# M891.net
KiCad netlist of a schematic drawn in EAGLE
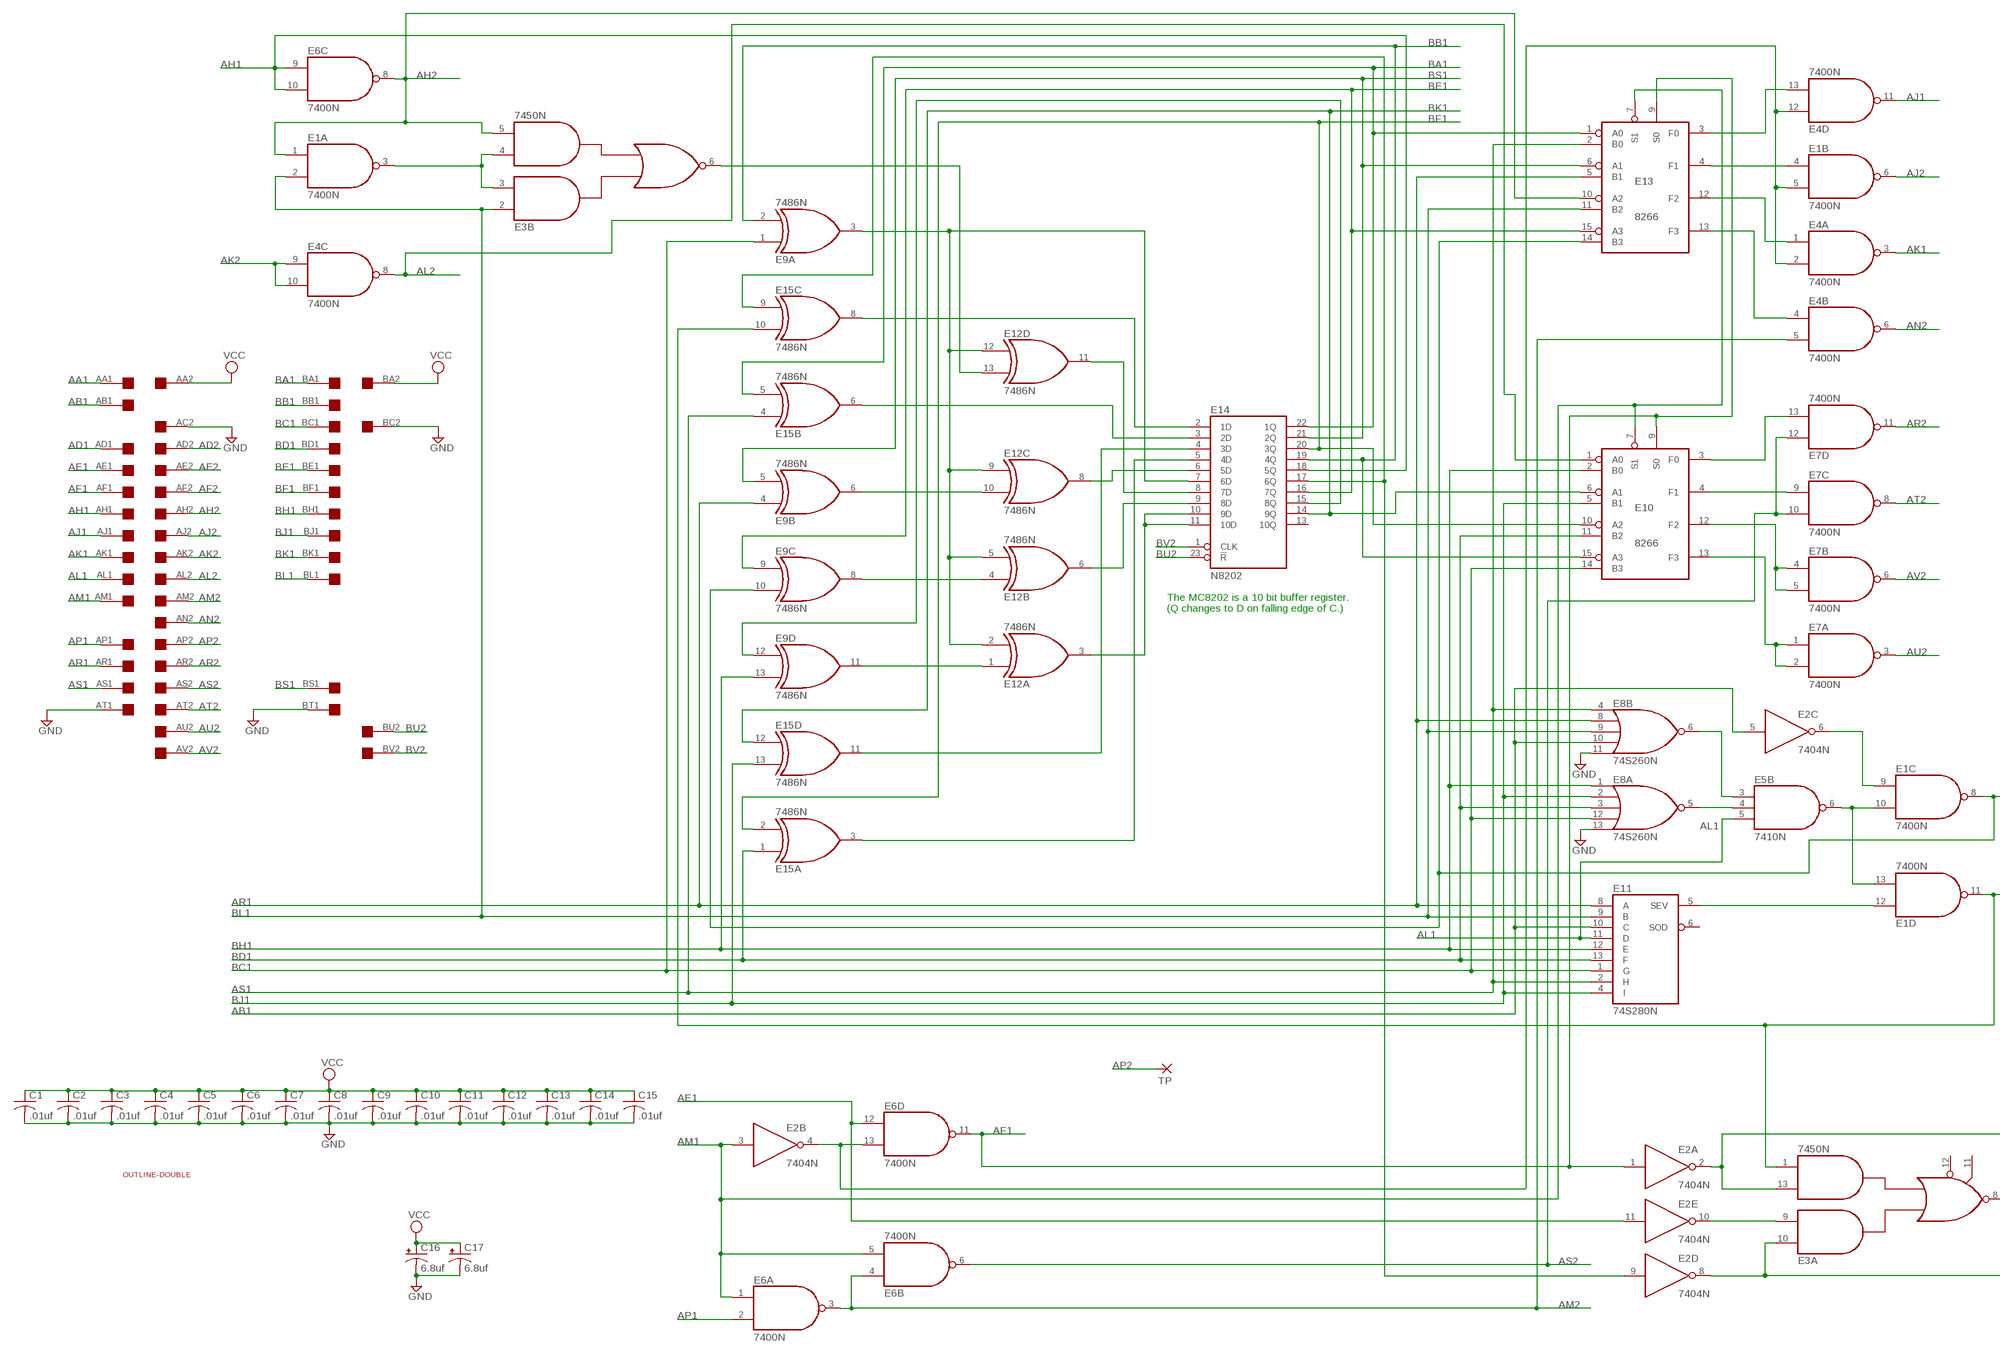
[diagram p0: schematic, sheet 1, part 1 of 2]
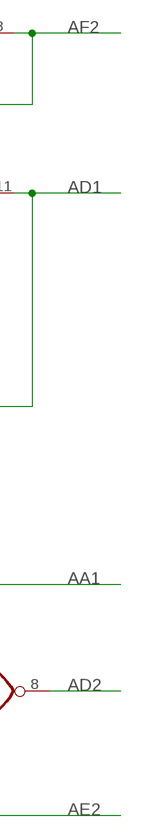
[diagram p1: schematic, sheet 1, part 2 of 2]

(export (version "E")
  (design (tool "Eeschema 10.0.6"))
  (components
    (comp (ref "C1")
      (value ".01uf")
      (footprint "eagle-import:C050-025X075")
      (libsource (lib "eagle-import") (part "C-US050-025X075"))
    )
    (comp (ref "C2")
      (value ".01uf")
      (footprint "eagle-import:C050-025X075")
      (libsource (lib "eagle-import") (part "C-US050-025X075"))
    )
    (comp (ref "C3")
      (value ".01uf")
      (footprint "eagle-import:C050-025X075")
      (libsource (lib "eagle-import") (part "C-US050-025X075"))
    )
    (comp (ref "C4")
      (value ".01uf")
      (footprint "eagle-import:C050-025X075")
      (libsource (lib "eagle-import") (part "C-US050-025X075"))
    )
    (comp (ref "C5")
      (value ".01uf")
      (footprint "eagle-import:C050-025X075")
      (libsource (lib "eagle-import") (part "C-US050-025X075"))
    )
    (comp (ref "C6")
      (value ".01uf")
      (footprint "eagle-import:C050-025X075")
      (libsource (lib "eagle-import") (part "C-US050-025X075"))
    )
    (comp (ref "C7")
      (value ".01uf")
      (footprint "eagle-import:C050-025X075")
      (libsource (lib "eagle-import") (part "C-US050-025X075"))
    )
    (comp (ref "C8")
      (value ".01uf")
      (footprint "eagle-import:C050-025X075")
      (libsource (lib "eagle-import") (part "C-US050-025X075"))
    )
    (comp (ref "C9")
      (value ".01uf")
      (footprint "eagle-import:C050-025X075")
      (libsource (lib "eagle-import") (part "C-US050-025X075"))
    )
    (comp (ref "C10")
      (value ".01uf")
      (footprint "eagle-import:C050-025X075")
      (libsource (lib "eagle-import") (part "C-US050-025X075"))
    )
    (comp (ref "C11")
      (value ".01uf")
      (footprint "eagle-import:C050-025X075")
      (libsource (lib "eagle-import") (part "C-US050-025X075"))
    )
    (comp (ref "C12")
      (value ".01uf")
      (footprint "eagle-import:C050-025X075")
      (libsource (lib "eagle-import") (part "C-US050-025X075"))
    )
    (comp (ref "C13")
      (value ".01uf")
      (footprint "eagle-import:C050-025X075")
      (libsource (lib "eagle-import") (part "C-US050-025X075"))
    )
    (comp (ref "C14")
      (value ".01uf")
      (footprint "eagle-import:C050-025X075")
      (libsource (lib "eagle-import") (part "C-US050-025X075"))
    )
    (comp (ref "C15")
      (value ".01uf")
      (footprint "eagle-import:C050-025X075")
      (libsource (lib "eagle-import") (part "C-US050-025X075"))
    )
    (comp (ref "C16")
      (value "6.8uf")
      (footprint "eagle-import:E22-6")
      (libsource (lib "eagle-import") (part "CPOL-USE22-6AXIAL"))
    )
    (comp (ref "C17")
      (value "6.8uf")
      (footprint "eagle-import:E22-6")
      (libsource (lib "eagle-import") (part "CPOL-USE22-6AXIAL"))
    )
    (comp (ref "E1")
      (value "7400N")
      (footprint "eagle-import:DIL14")
      (libsource (lib "eagle-import") (part "7400N"))
    )
    (comp (ref "E2")
      (value "7404N")
      (footprint "eagle-import:DIL14")
      (libsource (lib "eagle-import") (part "7404N"))
    )
    (comp (ref "E3")
      (value "7450N")
      (footprint "eagle-import:DIL14")
      (libsource (lib "eagle-import") (part "7450N"))
    )
    (comp (ref "E4")
      (value "7400N")
      (footprint "eagle-import:DIL14")
      (libsource (lib "eagle-import") (part "7400N"))
    )
    (comp (ref "E5")
      (value "7410N")
      (footprint "eagle-import:DIL14")
      (libsource (lib "eagle-import") (part "7410N"))
    )
    (comp (ref "E6")
      (value "7400N")
      (footprint "eagle-import:DIL14")
      (libsource (lib "eagle-import") (part "7400N"))
    )
    (comp (ref "E7")
      (value "7400N")
      (footprint "eagle-import:DIL14")
      (libsource (lib "eagle-import") (part "7400N"))
    )
    (comp (ref "E8")
      (value "74S260N")
      (footprint "eagle-import:DIL14")
      (libsource (lib "eagle-import") (part "74260NS"))
    )
    (comp (ref "E9")
      (value "7486N")
      (footprint "eagle-import:DIL14")
      (libsource (lib "eagle-import") (part "7486N"))
    )
    (comp (ref "E10")
      (value "8266")
      (footprint "eagle-import:DIL16")
      (libsource (lib "eagle-import") (part "8266"))
    )
    (comp (ref "E11")
      (value "74S280N")
      (footprint "eagle-import:DIL14")
      (libsource (lib "eagle-import") (part "74280NS"))
    )
    (comp (ref "E12")
      (value "7486N")
      (footprint "eagle-import:DIL14")
      (libsource (lib "eagle-import") (part "7486N"))
    )
    (comp (ref "E13")
      (value "8266")
      (footprint "eagle-import:DIL16")
      (libsource (lib "eagle-import") (part "8266"))
    )
    (comp (ref "E14")
      (value "N8202")
      (footprint "eagle-import:DIL24")
      (libsource (lib "eagle-import") (part "N8202"))
    )
    (comp (ref "E15")
      (value "7486N")
      (footprint "eagle-import:DIL14")
      (libsource (lib "eagle-import") (part "7486N"))
    )
    (comp (ref "EDGE")
      (value "DOUBLE")
      (footprint "eagle-import:EDGE-CON4")
      (libsource (lib "eagle-import") (part "DOUBLE"))
    )
    (comp (ref "TP")
      (value "2,15/1,0")
      (footprint "eagle-import:2,15_1,0")
      (libsource (lib "eagle-import") (part "2,15/1,0"))
    )
    (comp (ref "U$2")
      (value "OUTLINE-DOUBLE")
      (footprint "eagle-import:DOUBLE")
      (libsource (lib "eagle-import") (part "OUTLINE-DOUBLE"))
    )
  )
  (nets
    (net (code "1") (name "/AA1") (class "Default")
      (node (ref "E2") (pin "2") (pinfunction "O_2") (pintype "output"))
      (node (ref "E3") (pin "13") (pinfunction "I3_13") (pintype "input"))
      (node (ref "EDGE") (pin "AA1") (pinfunction "1_AA1") (pintype "bidirectional"))
    )
    (net (code "2") (name "/AB1") (class "Default")
      (node (ref "E11") (pin "10") (pinfunction "C_10") (pintype "input"))
      (node (ref "E2") (pin "5") (pinfunction "I_5") (pintype "input"))
      (node (ref "E8") (pin "10") (pinfunction "I3_10") (pintype "input"))
      (node (ref "EDGE") (pin "AB1") (pinfunction "1_AB1") (pintype "bidirectional"))
    )
    (net (code "3") (name "/AD1") (class "Default")
      (node (ref "E1") (pin "11") (pinfunction "O_11") (pintype "output"))
      (node (ref "E15") (pin "10") (pinfunction "I1_10") (pintype "input"))
      (node (ref "E3") (pin "1") (pinfunction "I4_1") (pintype "input"))
      (node (ref "EDGE") (pin "AD1") (pinfunction "1_AD1") (pintype "bidirectional"))
    )
    (net (code "4") (name "/AD2") (class "Default")
      (node (ref "E3") (pin "8") (pinfunction "O_8") (pintype "output"))
      (node (ref "EDGE") (pin "AD2") (pinfunction "1_AD2") (pintype "bidirectional"))
    )
    (net (code "5") (name "/AE1") (class "Default")
      (node (ref "E2") (pin "11") (pinfunction "I_11") (pintype "input"))
      (node (ref "E6") (pin "12") (pinfunction "I0_12") (pintype "input"))
      (node (ref "EDGE") (pin "AE1") (pinfunction "1_AE1") (pintype "bidirectional"))
    )
    (net (code "6") (name "/AE2") (class "Default")
      (node (ref "E2") (pin "8") (pinfunction "O_8") (pintype "output"))
      (node (ref "E3") (pin "10") (pinfunction "I1_10") (pintype "input"))
      (node (ref "EDGE") (pin "AE2") (pinfunction "1_AE2") (pintype "bidirectional"))
    )
    (net (code "7") (name "/AF1") (class "Default")
      (node (ref "E10") (pin "9") (pinfunction "S0_9") (pintype "input"))
      (node (ref "E13") (pin "9") (pinfunction "S0_9") (pintype "input"))
      (node (ref "E2") (pin "1") (pinfunction "I_1") (pintype "input"))
      (node (ref "E6") (pin "11") (pinfunction "O_11") (pintype "output"))
      (node (ref "EDGE") (pin "AF1") (pinfunction "1_AF1") (pintype "bidirectional"))
    )
    (net (code "8") (name "/AF2") (class "Default")
      (node (ref "E1") (pin "8") (pinfunction "O_8") (pintype "output"))
      (node (ref "E13") (pin "14") (pinfunction "B3_14") (pintype "input"))
      (node (ref "E9") (pin "10") (pinfunction "I1_10") (pintype "input"))
      (node (ref "EDGE") (pin "AF2") (pinfunction "1_AF2") (pintype "bidirectional"))
    )
    (net (code "9") (name "/AH1") (class "Default")
      (node (ref "E14") (pin "18") (pinfunction "5Q_18") (pintype "tri_state"))
      (node (ref "E6") (pin "10") (pinfunction "I1_10") (pintype "input"))
      (node (ref "E6") (pin "9") (pinfunction "I0_9") (pintype "input"))
      (node (ref "EDGE") (pin "AH1") (pinfunction "1_AH1") (pintype "bidirectional"))
    )
    (net (code "10") (name "/AH2") (class "Default")
      (node (ref "E1") (pin "1") (pinfunction "I0_1") (pintype "input"))
      (node (ref "E13") (pin "10") (pinfunction "A2_10") (pintype "input"))
      (node (ref "E3") (pin "5") (pinfunction "I4_5") (pintype "input"))
      (node (ref "E6") (pin "8") (pinfunction "O_8") (pintype "output"))
      (node (ref "EDGE") (pin "AH2") (pinfunction "1_AH2") (pintype "bidirectional"))
    )
    (net (code "11") (name "/AJ1") (class "Default")
      (node (ref "E4") (pin "11") (pinfunction "O_11") (pintype "output"))
      (node (ref "EDGE") (pin "AJ1") (pinfunction "1_AJ1") (pintype "bidirectional"))
    )
    (net (code "12") (name "/AJ2") (class "Default")
      (node (ref "E1") (pin "6") (pinfunction "O_6") (pintype "output"))
      (node (ref "EDGE") (pin "AJ2") (pinfunction "1_AJ2") (pintype "bidirectional"))
    )
    (net (code "13") (name "/AK1") (class "Default")
      (node (ref "E4") (pin "3") (pinfunction "O_3") (pintype "output"))
      (node (ref "EDGE") (pin "AK1") (pinfunction "1_AK1") (pintype "bidirectional"))
    )
    (net (code "14") (name "/AK2") (class "Default")
      (node (ref "E4") (pin "10") (pinfunction "I1_10") (pintype "input"))
      (node (ref "E4") (pin "9") (pinfunction "I0_9") (pintype "input"))
      (node (ref "EDGE") (pin "AK2") (pinfunction "1_AK2") (pintype "bidirectional"))
    )
    (net (code "15") (name "/AL1") (class "Default")
      (node (ref "E11") (pin "11") (pinfunction "D_11") (pintype "input"))
      (node (ref "E5") (pin "5") (pinfunction "I2_5") (pintype "input"))
      (node (ref "EDGE") (pin "AL1") (pinfunction "1_AL1") (pintype "bidirectional"))
    )
    (net (code "16") (name "/AL2") (class "Default")
      (node (ref "E10") (pin "1") (pinfunction "A0_1") (pintype "input"))
      (node (ref "E4") (pin "8") (pinfunction "O_8") (pintype "output"))
      (node (ref "EDGE") (pin "AL2") (pinfunction "1_AL2") (pintype "bidirectional"))
    )
    (net (code "17") (name "/AM1") (class "Default")
      (node (ref "E10") (pin "7") (pinfunction "S1_7") (pintype "input"))
      (node (ref "E13") (pin "7") (pinfunction "S1_7") (pintype "input"))
      (node (ref "E2") (pin "3") (pinfunction "I_3") (pintype "input"))
      (node (ref "E6") (pin "1") (pinfunction "I0_1") (pintype "input"))
      (node (ref "E6") (pin "5") (pinfunction "I1_5") (pintype "input"))
      (node (ref "EDGE") (pin "AM1") (pinfunction "1_AM1") (pintype "bidirectional"))
    )
    (net (code "18") (name "/AM2") (class "Default")
      (node (ref "E4") (pin "5") (pinfunction "I1_5") (pintype "input"))
      (node (ref "E6") (pin "3") (pinfunction "O_3") (pintype "output"))
      (node (ref "E6") (pin "4") (pinfunction "I0_4") (pintype "input"))
      (node (ref "EDGE") (pin "AM2") (pinfunction "1_AM2") (pintype "bidirectional"))
    )
    (net (code "19") (name "/AN2") (class "Default")
      (node (ref "E4") (pin "6") (pinfunction "O_6") (pintype "output"))
      (node (ref "EDGE") (pin "AN2") (pinfunction "1_AN2") (pintype "bidirectional"))
    )
    (net (code "20") (name "/AP1") (class "Default")
      (node (ref "E6") (pin "2") (pinfunction "I1_2") (pintype "input"))
      (node (ref "EDGE") (pin "AP1") (pinfunction "1_AP1") (pintype "bidirectional"))
    )
    (net (code "21") (name "/AP2") (class "Default")
      (node (ref "EDGE") (pin "AP2") (pinfunction "1_AP2") (pintype "bidirectional"))
      (node (ref "TP") (pin "1") (pinfunction "P_1") (pintype "passive"))
    )
    (net (code "22") (name "/AR1") (class "Default")
      (node (ref "E11") (pin "8") (pinfunction "A_8") (pintype "input"))
      (node (ref "E13") (pin "5") (pinfunction "B1_5") (pintype "input"))
      (node (ref "E8") (pin "8") (pinfunction "I1_8") (pintype "input"))
      (node (ref "E9") (pin "4") (pinfunction "I0_4") (pintype "input"))
      (node (ref "EDGE") (pin "AR1") (pinfunction "1_AR1") (pintype "bidirectional"))
    )
    (net (code "23") (name "/AR2") (class "Default")
      (node (ref "E7") (pin "11") (pinfunction "O_11") (pintype "output"))
      (node (ref "EDGE") (pin "AR2") (pinfunction "1_AR2") (pintype "bidirectional"))
    )
    (net (code "24") (name "/AS1") (class "Default")
      (node (ref "E11") (pin "2") (pinfunction "H_2") (pintype "input"))
      (node (ref "E13") (pin "2") (pinfunction "B0_2") (pintype "input"))
      (node (ref "E15") (pin "4") (pinfunction "I0_4") (pintype "input"))
      (node (ref "E8") (pin "4") (pinfunction "I0_4") (pintype "input"))
      (node (ref "EDGE") (pin "AS1") (pinfunction "1_AS1") (pintype "bidirectional"))
    )
    (net (code "25") (name "/AS2") (class "Default")
      (node (ref "E6") (pin "6") (pinfunction "O_6") (pintype "output"))
      (node (ref "E7") (pin "10") (pinfunction "I1_10") (pintype "input"))
      (node (ref "E7") (pin "12") (pinfunction "I0_12") (pintype "input"))
      (node (ref "EDGE") (pin "AS2") (pinfunction "1_AS2") (pintype "bidirectional"))
    )
    (net (code "26") (name "/AT2") (class "Default")
      (node (ref "E7") (pin "8") (pinfunction "O_8") (pintype "output"))
      (node (ref "EDGE") (pin "AT2") (pinfunction "1_AT2") (pintype "bidirectional"))
    )
    (net (code "27") (name "/AU2") (class "Default")
      (node (ref "E7") (pin "3") (pinfunction "O_3") (pintype "output"))
      (node (ref "EDGE") (pin "AU2") (pinfunction "1_AU2") (pintype "bidirectional"))
    )
    (net (code "28") (name "/AV2") (class "Default")
      (node (ref "E7") (pin "6") (pinfunction "O_6") (pintype "output"))
      (node (ref "EDGE") (pin "AV2") (pinfunction "1_AV2") (pintype "bidirectional"))
    )
    (net (code "29") (name "/BA1") (class "Default")
      (node (ref "E13") (pin "1") (pinfunction "A0_1") (pintype "input"))
      (node (ref "E14") (pin "22") (pinfunction "1Q_22") (pintype "tri_state"))
      (node (ref "E15") (pin "5") (pinfunction "I1_5") (pintype "input"))
      (node (ref "EDGE") (pin "BA1") (pinfunction "1_BA1") (pintype "bidirectional"))
    )
    (net (code "30") (name "/BB1") (class "Default")
      (node (ref "E10") (pin "15") (pinfunction "A3_15") (pintype "input"))
      (node (ref "E14") (pin "19") (pinfunction "4Q_19") (pintype "tri_state"))
      (node (ref "E9") (pin "2") (pinfunction "I1_2") (pintype "input"))
      (node (ref "EDGE") (pin "BB1") (pinfunction "1_BB1") (pintype "bidirectional"))
    )
    (net (code "31") (name "/BC1") (class "Default")
      (node (ref "E10") (pin "14") (pinfunction "B3_14") (pintype "input"))
      (node (ref "E11") (pin "1") (pinfunction "G_1") (pintype "input"))
      (node (ref "E8") (pin "12") (pinfunction "I3_12") (pintype "input"))
      (node (ref "E9") (pin "1") (pinfunction "I0_1") (pintype "input"))
      (node (ref "EDGE") (pin "BC1") (pinfunction "1_BC1") (pintype "bidirectional"))
    )
    (net (code "32") (name "/BD1") (class "Default")
      (node (ref "E10") (pin "11") (pinfunction "B2_11") (pintype "input"))
      (node (ref "E11") (pin "13") (pinfunction "F_13") (pintype "input"))
      (node (ref "E15") (pin "1") (pinfunction "I0_1") (pintype "input"))
      (node (ref "E8") (pin "3") (pinfunction "I2_3") (pintype "input"))
      (node (ref "EDGE") (pin "BD1") (pinfunction "1_BD1") (pintype "bidirectional"))
    )
    (net (code "33") (name "/BE1") (class "Default")
      (node (ref "E13") (pin "15") (pinfunction "A3_15") (pintype "input"))
      (node (ref "E14") (pin "16") (pinfunction "7Q_16") (pintype "tri_state"))
      (node (ref "E9") (pin "9") (pinfunction "I0_9") (pintype "input"))
      (node (ref "EDGE") (pin "BE1") (pinfunction "1_BE1") (pintype "bidirectional"))
    )
    (net (code "34") (name "/BF1") (class "Default")
      (node (ref "E10") (pin "10") (pinfunction "A2_10") (pintype "input"))
      (node (ref "E14") (pin "20") (pinfunction "3Q_20") (pintype "tri_state"))
      (node (ref "E15") (pin "2") (pinfunction "I1_2") (pintype "input"))
      (node (ref "EDGE") (pin "BF1") (pinfunction "1_BF1") (pintype "bidirectional"))
    )
    (net (code "35") (name "/BH1") (class "Default")
      (node (ref "E10") (pin "2") (pinfunction "B0_2") (pintype "input"))
      (node (ref "E11") (pin "12") (pinfunction "E_12") (pintype "input"))
      (node (ref "E8") (pin "1") (pinfunction "I0_1") (pintype "input"))
      (node (ref "E9") (pin "13") (pinfunction "I1_13") (pintype "input"))
      (node (ref "EDGE") (pin "BH1") (pinfunction "1_BH1") (pintype "bidirectional"))
    )
    (net (code "36") (name "/BJ1") (class "Default")
      (node (ref "E10") (pin "5") (pinfunction "B1_5") (pintype "input"))
      (node (ref "E11") (pin "4") (pinfunction "I_4") (pintype "input"))
      (node (ref "E15") (pin "13") (pinfunction "I1_13") (pintype "input"))
      (node (ref "E8") (pin "2") (pinfunction "I1_2") (pintype "input"))
      (node (ref "EDGE") (pin "BJ1") (pinfunction "1_BJ1") (pintype "bidirectional"))
    )
    (net (code "37") (name "/BK1") (class "Default")
      (node (ref "E10") (pin "6") (pinfunction "A1_6") (pintype "input"))
      (node (ref "E14") (pin "14") (pinfunction "9Q_14") (pintype "tri_state"))
      (node (ref "E15") (pin "12") (pinfunction "I0_12") (pintype "input"))
      (node (ref "EDGE") (pin "BK1") (pinfunction "1_BK1") (pintype "bidirectional"))
    )
    (net (code "38") (name "/BL1") (class "Default")
      (node (ref "E1") (pin "2") (pinfunction "I1_2") (pintype "input"))
      (node (ref "E11") (pin "9") (pinfunction "B_9") (pintype "input"))
      (node (ref "E13") (pin "11") (pinfunction "B2_11") (pintype "input"))
      (node (ref "E3") (pin "2") (pinfunction "I1_2") (pintype "input"))
      (node (ref "E8") (pin "9") (pinfunction "I2_9") (pintype "input"))
      (node (ref "EDGE") (pin "BL1") (pinfunction "1_BL1") (pintype "bidirectional"))
    )
    (net (code "39") (name "/BS1") (class "Default")
      (node (ref "E13") (pin "6") (pinfunction "A1_6") (pintype "input"))
      (node (ref "E14") (pin "21") (pinfunction "2Q_21") (pintype "tri_state"))
      (node (ref "E9") (pin "5") (pinfunction "I1_5") (pintype "input"))
      (node (ref "EDGE") (pin "BS1") (pinfunction "1_BS1") (pintype "bidirectional"))
    )
    (net (code "40") (name "/BU2") (class "Default")
      (node (ref "E14") (pin "23") (pinfunction "~{R}_23") (pintype "input"))
      (node (ref "EDGE") (pin "BU2") (pinfunction "1_BU2") (pintype "bidirectional"))
    )
    (net (code "41") (name "/BV2") (class "Default")
      (node (ref "E14") (pin "1") (pinfunction "CLK_1") (pintype "input"))
      (node (ref "EDGE") (pin "BV2") (pinfunction "1_BV2") (pintype "bidirectional"))
    )
    (net (code "42") (name "GND") (class "Default")
      (node (ref "C1") (pin "2") (pinfunction "2_2") (pintype "passive"))
      (node (ref "C10") (pin "2") (pinfunction "2_2") (pintype "passive"))
      (node (ref "C11") (pin "2") (pinfunction "2_2") (pintype "passive"))
      (node (ref "C12") (pin "2") (pinfunction "2_2") (pintype "passive"))
      (node (ref "C13") (pin "2") (pinfunction "2_2") (pintype "passive"))
      (node (ref "C14") (pin "2") (pinfunction "2_2") (pintype "passive"))
      (node (ref "C15") (pin "2") (pinfunction "2_2") (pintype "passive"))
      (node (ref "C16") (pin "-") (pinfunction "-_-") (pintype "passive"))
      (node (ref "C17") (pin "-") (pinfunction "-_-") (pintype "passive"))
      (node (ref "C2") (pin "2") (pinfunction "2_2") (pintype "passive"))
      (node (ref "C3") (pin "2") (pinfunction "2_2") (pintype "passive"))
      (node (ref "C4") (pin "2") (pinfunction "2_2") (pintype "passive"))
      (node (ref "C5") (pin "2") (pinfunction "2_2") (pintype "passive"))
      (node (ref "C6") (pin "2") (pinfunction "2_2") (pintype "passive"))
      (node (ref "C7") (pin "2") (pinfunction "2_2") (pintype "passive"))
      (node (ref "C8") (pin "2") (pinfunction "2_2") (pintype "passive"))
      (node (ref "C9") (pin "2") (pinfunction "2_2") (pintype "passive"))
      (node (ref "E8") (pin "11") (pinfunction "I4_11") (pintype "input"))
      (node (ref "E8") (pin "13") (pinfunction "I4_13") (pintype "input"))
      (node (ref "EDGE") (pin "AC2") (pinfunction "1_AC2") (pintype "bidirectional"))
      (node (ref "EDGE") (pin "AT1") (pinfunction "1_AT1") (pintype "bidirectional"))
      (node (ref "EDGE") (pin "BC2") (pinfunction "1_BC2") (pintype "bidirectional"))
      (node (ref "EDGE") (pin "BT1") (pinfunction "1_BT1") (pintype "bidirectional"))
    )
    (net (code "43") (name "Net-(E1A-O)") (class "Default")
      (node (ref "E1") (pin "3") (pinfunction "O_3") (pintype "output"))
      (node (ref "E3") (pin "3") (pinfunction "I2_3") (pintype "input"))
      (node (ref "E3") (pin "4") (pinfunction "I3_4") (pintype "input"))
    )
    (net (code "44") (name "Net-(E1B-I1)") (class "Default")
      (node (ref "E1") (pin "5") (pinfunction "I1_5") (pintype "input"))
      (node (ref "E2") (pin "4") (pinfunction "O_4") (pintype "output"))
      (node (ref "E4") (pin "12") (pinfunction "I0_12") (pintype "input"))
      (node (ref "E4") (pin "2") (pinfunction "I1_2") (pintype "input"))
      (node (ref "E6") (pin "13") (pinfunction "I1_13") (pintype "input"))
    )
    (net (code "45") (name "Net-(E1C-I0)") (class "Default")
      (node (ref "E1") (pin "9") (pinfunction "I0_9") (pintype "input"))
      (node (ref "E2") (pin "6") (pinfunction "O_6") (pintype "output"))
    )
    (net (code "46") (name "Net-(E1C-I1)") (class "Default")
      (node (ref "E1") (pin "10") (pinfunction "I1_10") (pintype "input"))
      (node (ref "E1") (pin "13") (pinfunction "I1_13") (pintype "input"))
      (node (ref "E5") (pin "6") (pinfunction "O_6") (pintype "output"))
    )
    (net (code "47") (name "Net-(E2E-O)") (class "Default")
      (node (ref "E2") (pin "10") (pinfunction "O_10") (pintype "output"))
      (node (ref "E3") (pin "9") (pinfunction "I2_9") (pintype "input"))
    )
    (net (code "48") (name "Net-(E5B-I0)") (class "Default")
      (node (ref "E5") (pin "3") (pinfunction "I0_3") (pintype "input"))
      (node (ref "E8") (pin "6") (pinfunction "O_6") (pintype "output"))
    )
    (net (code "49") (name "Net-(E5B-I1)") (class "Default")
      (node (ref "E5") (pin "4") (pinfunction "I1_4") (pintype "input"))
      (node (ref "E8") (pin "5") (pinfunction "O_5") (pintype "output"))
    )
    (net (code "50") (name "Net-(E10A-F0)") (class "Default")
      (node (ref "E10") (pin "3") (pinfunction "F0_3") (pintype "output"))
      (node (ref "E7") (pin "13") (pinfunction "I1_13") (pintype "input"))
    )
    (net (code "51") (name "Net-(E10A-F1)") (class "Default")
      (node (ref "E10") (pin "4") (pinfunction "F1_4") (pintype "output"))
      (node (ref "E7") (pin "9") (pinfunction "I0_9") (pintype "input"))
    )
    (net (code "52") (name "Net-(E10A-F2)") (class "Default")
      (node (ref "E10") (pin "12") (pinfunction "F2_12") (pintype "output"))
      (node (ref "E7") (pin "4") (pinfunction "I0_4") (pintype "input"))
      (node (ref "E7") (pin "5") (pinfunction "I1_5") (pintype "input"))
    )
    (net (code "53") (name "Net-(E10A-F3)") (class "Default")
      (node (ref "E10") (pin "13") (pinfunction "F3_13") (pintype "output"))
      (node (ref "E7") (pin "1") (pinfunction "I0_1") (pintype "input"))
      (node (ref "E7") (pin "2") (pinfunction "I1_2") (pintype "input"))
    )
    (net (code "54") (name "Net-(E11A-SEV)") (class "Default")
      (node (ref "E1") (pin "12") (pinfunction "I0_12") (pintype "input"))
      (node (ref "E11") (pin "5") (pinfunction "SEV_5") (pintype "output"))
    )
    (net (code "55") (name "Net-(E12A-I0)") (class "Default")
      (node (ref "E12") (pin "1") (pinfunction "I0_1") (pintype "input"))
      (node (ref "E9") (pin "11") (pinfunction "O_11") (pintype "output"))
    )
    (net (code "56") (name "Net-(E12A-I1)") (class "Default")
      (node (ref "E12") (pin "12") (pinfunction "I0_12") (pintype "input"))
      (node (ref "E12") (pin "2") (pinfunction "I1_2") (pintype "input"))
      (node (ref "E12") (pin "5") (pinfunction "I1_5") (pintype "input"))
      (node (ref "E12") (pin "9") (pinfunction "I0_9") (pintype "input"))
      (node (ref "E14") (pin "7") (pinfunction "6D_7") (pintype "input"))
      (node (ref "E9") (pin "3") (pinfunction "O_3") (pintype "output"))
    )
    (net (code "57") (name "Net-(E12A-O)") (class "Default")
      (node (ref "E12") (pin "3") (pinfunction "O_3") (pintype "output"))
      (node (ref "E14") (pin "10") (pinfunction "9D_10") (pintype "input"))
      (node (ref "E14") (pin "11") (pinfunction "10D_11") (pintype "input"))
    )
    (net (code "58") (name "Net-(E12B-I0)") (class "Default")
      (node (ref "E12") (pin "4") (pinfunction "I0_4") (pintype "input"))
      (node (ref "E9") (pin "8") (pinfunction "O_8") (pintype "output"))
    )
    (net (code "59") (name "Net-(E12B-O)") (class "Default")
      (node (ref "E12") (pin "6") (pinfunction "O_6") (pintype "output"))
      (node (ref "E14") (pin "9") (pinfunction "8D_9") (pintype "input"))
    )
    (net (code "60") (name "Net-(E12C-I1)") (class "Default")
      (node (ref "E12") (pin "10") (pinfunction "I1_10") (pintype "input"))
      (node (ref "E9") (pin "6") (pinfunction "O_6") (pintype "output"))
    )
    (net (code "61") (name "Net-(E12C-O)") (class "Default")
      (node (ref "E12") (pin "8") (pinfunction "O_8") (pintype "output"))
      (node (ref "E14") (pin "6") (pinfunction "5D_6") (pintype "input"))
    )
    (net (code "62") (name "Net-(E12D-I1)") (class "Default")
      (node (ref "E12") (pin "13") (pinfunction "I1_13") (pintype "input"))
      (node (ref "E3") (pin "6") (pinfunction "O_6") (pintype "output"))
    )
    (net (code "63") (name "Net-(E12D-O)") (class "Default")
      (node (ref "E12") (pin "11") (pinfunction "O_11") (pintype "output"))
      (node (ref "E14") (pin "8") (pinfunction "7D_8") (pintype "input"))
    )
    (net (code "64") (name "Net-(E13A-F0)") (class "Default")
      (node (ref "E13") (pin "3") (pinfunction "F0_3") (pintype "output"))
      (node (ref "E4") (pin "13") (pinfunction "I1_13") (pintype "input"))
    )
    (net (code "65") (name "Net-(E13A-F1)") (class "Default")
      (node (ref "E1") (pin "4") (pinfunction "I0_4") (pintype "input"))
      (node (ref "E13") (pin "4") (pinfunction "F1_4") (pintype "output"))
    )
    (net (code "66") (name "Net-(E13A-F2)") (class "Default")
      (node (ref "E13") (pin "12") (pinfunction "F2_12") (pintype "output"))
      (node (ref "E4") (pin "1") (pinfunction "I0_1") (pintype "input"))
    )
    (net (code "67") (name "Net-(E13A-F3)") (class "Default")
      (node (ref "E13") (pin "13") (pinfunction "F3_13") (pintype "output"))
      (node (ref "E4") (pin "4") (pinfunction "I0_4") (pintype "input"))
    )
    (net (code "68") (name "Net-(E14A-1D)") (class "Default")
      (node (ref "E14") (pin "2") (pinfunction "1D_2") (pintype "input"))
      (node (ref "E15") (pin "8") (pinfunction "O_8") (pintype "output"))
    )
    (net (code "69") (name "Net-(E14A-2D)") (class "Default")
      (node (ref "E14") (pin "3") (pinfunction "2D_3") (pintype "input"))
      (node (ref "E15") (pin "6") (pinfunction "O_6") (pintype "output"))
    )
    (net (code "70") (name "Net-(E14A-3D)") (class "Default")
      (node (ref "E14") (pin "4") (pinfunction "3D_4") (pintype "input"))
      (node (ref "E15") (pin "11") (pinfunction "O_11") (pintype "output"))
    )
    (net (code "71") (name "Net-(E14A-4D)") (class "Default")
      (node (ref "E14") (pin "5") (pinfunction "4D_5") (pintype "input"))
      (node (ref "E15") (pin "3") (pinfunction "O_3") (pintype "output"))
    )
    (net (code "72") (name "Net-(E14A-6Q)") (class "Default")
      (node (ref "E14") (pin "17") (pinfunction "6Q_17") (pintype "tri_state"))
      (node (ref "E15") (pin "9") (pinfunction "I0_9") (pintype "input"))
      (node (ref "E2") (pin "9") (pinfunction "I_9") (pintype "input"))
    )
    (net (code "73") (name "Net-(E14A-8Q)") (class "Default")
      (node (ref "E14") (pin "15") (pinfunction "8Q_15") (pintype "tri_state"))
      (node (ref "E9") (pin "12") (pinfunction "I0_12") (pintype "input"))
    )
    (net (code "74") (name "VCC") (class "Default")
      (node (ref "C1") (pin "1") (pinfunction "1_1") (pintype "passive"))
      (node (ref "C10") (pin "1") (pinfunction "1_1") (pintype "passive"))
      (node (ref "C11") (pin "1") (pinfunction "1_1") (pintype "passive"))
      (node (ref "C12") (pin "1") (pinfunction "1_1") (pintype "passive"))
      (node (ref "C13") (pin "1") (pinfunction "1_1") (pintype "passive"))
      (node (ref "C14") (pin "1") (pinfunction "1_1") (pintype "passive"))
      (node (ref "C15") (pin "1") (pinfunction "1_1") (pintype "passive"))
      (node (ref "C16") (pin "+") (pinfunction "+_+") (pintype "passive"))
      (node (ref "C17") (pin "+") (pinfunction "+_+") (pintype "passive"))
      (node (ref "C2") (pin "1") (pinfunction "1_1") (pintype "passive"))
      (node (ref "C3") (pin "1") (pinfunction "1_1") (pintype "passive"))
      (node (ref "C4") (pin "1") (pinfunction "1_1") (pintype "passive"))
      (node (ref "C5") (pin "1") (pinfunction "1_1") (pintype "passive"))
      (node (ref "C6") (pin "1") (pinfunction "1_1") (pintype "passive"))
      (node (ref "C7") (pin "1") (pinfunction "1_1") (pintype "passive"))
      (node (ref "C8") (pin "1") (pinfunction "1_1") (pintype "passive"))
      (node (ref "C9") (pin "1") (pinfunction "1_1") (pintype "passive"))
      (node (ref "EDGE") (pin "AA2") (pinfunction "1_AA2") (pintype "bidirectional"))
      (node (ref "EDGE") (pin "BA2") (pinfunction "1_BA2") (pintype "bidirectional"))
    )
    (net (code "75") (name "unconnected-(E3A-I5-Pad12)") (class "Default")
      (node (ref "E3") (pin "12") (pinfunction "I5_12") (pintype "passive"))
    )
    (net (code "76") (name "unconnected-(E3A-I6-Pad11)") (class "Default")
      (node (ref "E3") (pin "11") (pinfunction "I6_11") (pintype "passive"))
    )
    (net (code "77") (name "unconnected-(E11A-SOD-Pad6)") (class "Default")
      (node (ref "E11") (pin "6") (pinfunction "SOD_6") (pintype "output"))
    )
    (net (code "78") (name "unconnected-(E14A-10Q-Pad13)") (class "Default")
      (node (ref "E14") (pin "13") (pinfunction "10Q_13") (pintype "tri_state"))
    )
  )
)
